# power.net
KiCad netlist of a schematic drawn in Altium Designer
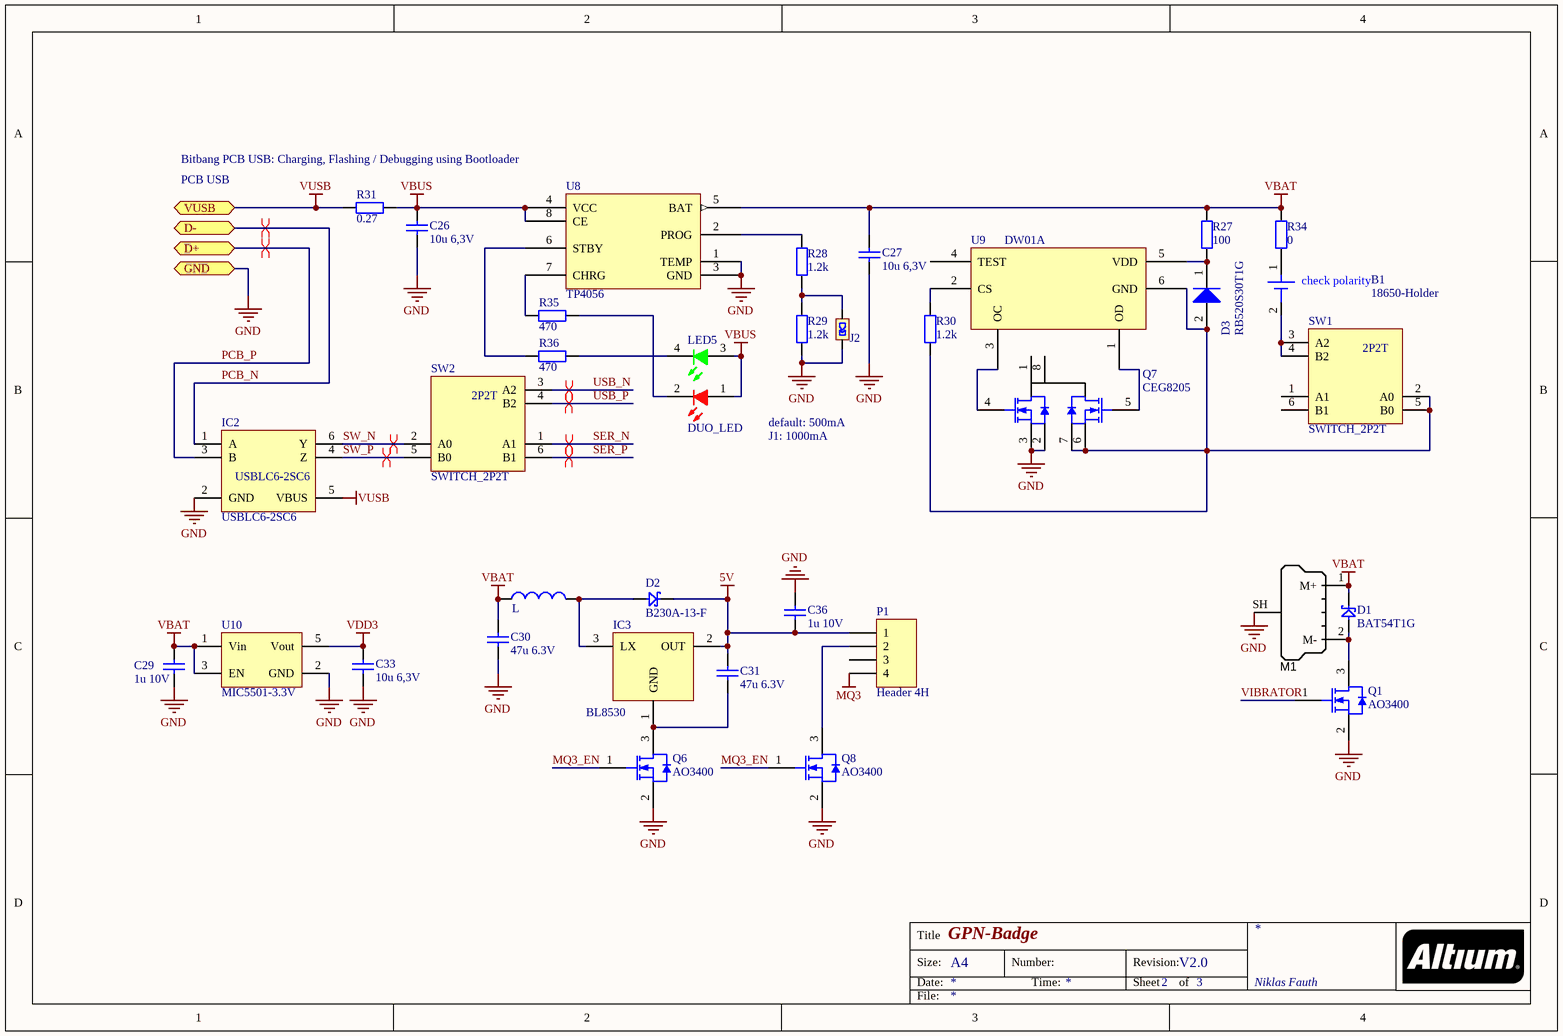
[diagram p0: power.SchDoc]

(export (version "E")
  (design (tool "Eeschema 10.0.6"))
  (components
    (comp (ref "B1")
      (value "18650-Holder")
      (footprint "18650–Holder-SMD")
      (libsource (lib "gpn-badge") (part "18650–Holder"))
    )
    (comp (ref "C26")
      (value "10u 6,3V")
      (footprint "C-0603-H")
      (description "Capacitor 10uF 6,3V")
      (libsource (lib "Passives") (part "C-0603-10u-6,3V"))
    )
    (comp (ref "C27")
      (value "10u 6,3V")
      (footprint "C-0603-H")
      (description "Capacitor 10uF 6,3V")
      (libsource (lib "Passives") (part "C-0603-10u-6,3V"))
    )
    (comp (ref "C29")
      (value "1u 10V")
      (footprint "C-0603-M")
      (description "Capacitor 1uF 10V")
      (libsource (lib "Passives") (part "C-0603-1u-10V"))
    )
    (comp (ref "C30")
      (value "47u 6.3V")
      (footprint "C-0805-M")
      (description "Capacitor 47u 6.3V")
      (libsource (lib "Passives") (part "C-0805-47u-6.3V"))
    )
    (comp (ref "C31")
      (value "47u 6.3V")
      (footprint "C-0805-M")
      (description "Capacitor 47u 6.3V")
      (libsource (lib "Passives") (part "C-0805-47u-6.3V"))
    )
    (comp (ref "C33")
      (value "10u 6,3V")
      (footprint "C-0603-H")
      (description "Capacitor 10uF 6,3V")
      (libsource (lib "Passives") (part "C-0603-10u-6,3V"))
    )
    (comp (ref "C36")
      (value "1u 10V")
      (footprint "C-0603-M")
      (description "Capacitor 1uF 10V")
      (libsource (lib "Passives") (part "C-0603-1u-10V"))
    )
    (comp (ref "D1") (value "BAT54T1G") (footprint "SOD123") (libsource (lib "advanced") (part "D-BAT54T1G")))
    (comp (ref "D2")
      (value "B230A-13-F")
      (footprint "DIODE-SMA")
      (libsource (lib "advanced") (part "D-B230A-13-F"))
    )
    (comp (ref "D3")
      (value "RB520S30T1G")
      (footprint "ONSC-SOD-523-2-502-01_V")
      (description "Schottky Barrier Diode, 2-Pin SOD-523, Pb-Free, Tape and Reel")
      (fields (field (name "MANUFACTURER") "On Semiconductor"))
      (libsource (lib "Altium Content Vault") (part "ONSC-D-K1A2-2"))
    )
    (comp (ref "IC2")
      (value "USBLC6-2SC6")
      (footprint "SOT23-6")
      (description "USB protection")
      (libsource (lib "gpn-badge") (part "USBLC6-2SC6"))
    )
    (comp (ref "IC3")
      (value "BL8530")
      (footprint "SOT89-150P409X160-3N")
      (libsource (lib "gpn-badge") (part "BL8530"))
    )
    (comp (ref "J2")
      (value "jumper")
      (footprint "JUMPER 1-1")
      (libsource (lib "advanced") (part "jumper 1-1"))
    )
    (comp (ref "L1") (value "L") (footprint "L") (libsource (lib "gpn-badge") (part "L")))
    (comp (ref "LED5") (value "DUO_LED") (footprint "LEDDUO") (libsource (lib "gpn-badge") (part "DUO_LED")))
    (comp (ref "M1")
      (value "VIBRATOR")
      (footprint "VIBRATOR_SMD")
      (description "rawr")
      (libsource (lib "gpn-badge") (part "VIBRATOR"))
    )
    (comp (ref "P1")
      (value "Header 4H")
      (footprint "HDR1X4H")
      (description "Header, 4-Pin, Right Angle")
      (fields (field (name "PUBLISHER") "Altium Limited"))
      (libsource (lib "gpn-badge") (part "Header 4H"))
    )
    (comp (ref "Q1")
      (value "AO3400")
      (footprint "AO-SOT23-3_V")
      (description "N-channel Enhancement Mode Field-Effect Transistor; 5.8A/30V")
      (fields (field (name "MANUFACTURER") "Alpha and Omega"))
      (libsource (lib "Altium Content Vault") (part "AO-NEMOS-G1S2D3-3"))
    )
    (comp (ref "Q6")
      (value "AO3400")
      (footprint "AO-SOT23-3_V")
      (description "N-channel Enhancement Mode Field-Effect Transistor; 5.8A/30V")
      (fields (field (name "MANUFACTURER") "Alpha and Omega"))
      (libsource (lib "Altium Content Vault") (part "AO-NEMOS-G1S2D3-3"))
    )
    (comp (ref "Q7")
      (value "CEG8205")
      (footprint "SOP64P640X265-8N")
      (description "Dual mini mosfet 20V 4.5A")
      (libsource (lib "gpn-badge") (part "MOSFET-CEG8205"))
    )
    (comp (ref "Q8")
      (value "AO3400")
      (footprint "AO-SOT23-3_V")
      (description "N-channel Enhancement Mode Field-Effect Transistor; 5.8A/30V")
      (fields (field (name "MANUFACTURER") "Alpha and Omega"))
      (libsource (lib "Altium Content Vault") (part "AO-NEMOS-G1S2D3-3"))
    )
    (comp (ref "R27")
      (value "100")
      (footprint "R-0603-M")
      (description "Resistor 100")
      (libsource (lib "Passives") (part "R-0603-100"))
    )
    (comp (ref "R28")
      (value "1.2k")
      (footprint "R-0603-M")
      (description "Resistor 1.2k")
      (libsource (lib "Passives") (part "R-0603-1k2"))
    )
    (comp (ref "R29")
      (value "1.2k")
      (footprint "R-0603-M")
      (description "Resistor 1.2k")
      (libsource (lib "Passives") (part "R-0603-1k2"))
    )
    (comp (ref "R30")
      (value "1.2k")
      (footprint "R-0603-M")
      (description "Resistor 1.2k")
      (libsource (lib "Passives") (part "R-0603-1k2"))
    )
    (comp (ref "R31")
      (value "0.27")
      (footprint "R-1206-M")
      (description "Resistor 0.27")
      (libsource (lib "Passives") (part "R-1206-0R27"))
    )
    (comp (ref "R34")
      (value "0")
      (footprint "R-0603-M")
      (description "Resistor 0")
      (libsource (lib "Passives") (part "R-0603-0"))
    )
    (comp (ref "R35")
      (value "470")
      (footprint "R-0603-M")
      (description "Resistor 470")
      (libsource (lib "Passives") (part "R-0603-470"))
    )
    (comp (ref "R36")
      (value "470")
      (footprint "R-0603-M")
      (description "Resistor 470")
      (libsource (lib "Passives") (part "R-0603-470"))
    )
    (comp (ref "SW1")
      (value "SWITCH_2P2T")
      (footprint "SWITCH_THT")
      (libsource (lib "gpn-badge") (part "SWITCH_2P2T"))
    )
    (comp (ref "SW2")
      (value "SWITCH_2P2T")
      (footprint "SWITCH_THT")
      (libsource (lib "") (part "SWITCH_2P2T_1"))
    )
    (comp (ref "U8")
      (value "TP4056")
      (footprint "SOIC127P600X20_HS-9N")
      (description "1A standalone linear charging IC")
      (libsource (lib "advanced") (part "TP4056"))
    )
    (comp (ref "U9")
      (value "DW01A")
      (footprint "SOT23-6")
      (description "Single Cell LiIon LiPo Protection")
      (libsource (lib "advanced") (part "DW01A"))
    )
    (comp (ref "U10")
      (value "MIC5501-3.3V")
      (footprint "SOT23-5")
      (libsource (lib "advanced") (part "MIC5501-3.3V"))
    )
  )
  (nets
    (net (code "1") (name "/MQ3_EN") (class "Default")
      (node (ref "Q6") (pin "1") (pinfunction "G_1") (pintype "passive"))
      (node (ref "Q8") (pin "1") (pinfunction "G_1") (pintype "passive"))
    )
    (net (code "2") (name "/PCB_N") (class "Default")
      (node (ref "IC2") (pin "1") (pinfunction "A_1") (pintype "passive"))
    )
    (net (code "3") (name "/PCB_P") (class "Default")
      (node (ref "IC2") (pin "3") (pinfunction "B_3") (pintype "passive"))
    )
    (net (code "4") (name "/SER_N") (class "Default")
      (node (ref "SW2") (pin "1") (pinfunction "A1_1") (pintype "passive"))
    )
    (net (code "5") (name "/SER_P") (class "Default")
      (node (ref "SW2") (pin "6") (pinfunction "B1_6") (pintype "passive"))
    )
    (net (code "6") (name "/SW_N") (class "Default")
      (node (ref "IC2") (pin "6") (pinfunction "Y_6") (pintype "passive"))
      (node (ref "SW2") (pin "2") (pinfunction "A0_2") (pintype "passive"))
    )
    (net (code "7") (name "/SW_P") (class "Default")
      (node (ref "IC2") (pin "4") (pinfunction "Z_4") (pintype "passive"))
      (node (ref "SW2") (pin "5") (pinfunction "B0_5") (pintype "passive"))
    )
    (net (code "8") (name "/USB_N") (class "Default")
      (node (ref "SW2") (pin "3") (pinfunction "A2_3") (pintype "passive"))
    )
    (net (code "9") (name "/USB_P") (class "Default")
      (node (ref "SW2") (pin "4") (pinfunction "B2_4") (pintype "passive"))
    )
    (net (code "10") (name "/VIBRATOR") (class "Default")
      (node (ref "Q1") (pin "1") (pinfunction "G_1") (pintype "passive"))
    )
    (net (code "11") (name "5V") (class "Default")
      (node (ref "C31") (pin "2") (pinfunction "2_2") (pintype "passive"))
      (node (ref "C36") (pin "2") (pinfunction "2_2") (pintype "passive"))
      (node (ref "D2") (pin "2") (pinfunction "kt_2") (pintype "passive"))
      (node (ref "IC3") (pin "2") (pinfunction "OUT_2") (pintype "passive"))
      (node (ref "P1") (pin "1") (pinfunction "1_1") (pintype "passive"))
    )
    (net (code "12") (name "GND") (class "Default")
      (node (ref "C26") (pin "1") (pinfunction "1_1") (pintype "passive"))
      (node (ref "C27") (pin "1") (pinfunction "1_1") (pintype "passive"))
      (node (ref "C29") (pin "1") (pinfunction "1_1") (pintype "passive"))
      (node (ref "C30") (pin "1") (pinfunction "1_1") (pintype "passive"))
      (node (ref "C33") (pin "1") (pinfunction "1_1") (pintype "passive"))
      (node (ref "C36") (pin "1") (pinfunction "1_1") (pintype "passive"))
      (node (ref "IC2") (pin "2") (pinfunction "GND_2") (pintype "passive"))
      (node (ref "J2") (pin "2") (pintype "passive"))
      (node (ref "M1") (pin "SH") (pinfunction "Shell_SH") (pintype "passive"))
      (node (ref "Q1") (pin "2") (pinfunction "S_2") (pintype "passive"))
      (node (ref "Q6") (pin "2") (pinfunction "S_2") (pintype "passive"))
      (node (ref "Q7") (pin "2") (pinfunction "S1_2") (pintype "passive"))
      (node (ref "Q7") (pin "3") (pinfunction "S1_3") (pintype "passive"))
      (node (ref "Q8") (pin "2") (pinfunction "S_2") (pintype "passive"))
      (node (ref "R29") (pin "1") (pinfunction "1_1") (pintype "passive"))
      (node (ref "U10") (pin "2") (pinfunction "GND_2") (pintype "passive"))
      (node (ref "U8") (pin "1") (pinfunction "TEMP_1") (pintype "passive"))
      (node (ref "U8") (pin "3") (pinfunction "GND_3") (pintype "power_in"))
    )
    (net (code "13") (name "MQ3") (class "Default")
      (node (ref "P1") (pin "4") (pinfunction "4_4") (pintype "passive"))
    )
    (net (code "14") (name "Net-(B1-Pad1)") (class "Default")
      (node (ref "B1") (pin "1") (pintype "passive"))
      (node (ref "R34") (pin "1") (pinfunction "1_1") (pintype "passive"))
    )
    (net (code "15") (name "Net-(D1-an)") (class "Default")
      (node (ref "D1") (pin "1") (pinfunction "an_1") (pintype "passive"))
      (node (ref "M1") (pin "2") (pinfunction "M-_2") (pintype "passive"))
      (node (ref "Q1") (pin "3") (pinfunction "D_3") (pintype "passive"))
    )
    (net (code "16") (name "Net-(D2-an)") (class "Default")
      (node (ref "D2") (pin "1") (pinfunction "an_1") (pintype "passive"))
      (node (ref "IC3") (pin "3") (pinfunction "LX_3") (pintype "passive"))
      (node (ref "L1") (pin "2") (pinfunction "2_2") (pintype "passive"))
    )
    (net (code "17") (name "Net-(D3-A)") (class "Default")
      (node (ref "D3") (pin "2") (pinfunction "A_2") (pintype "passive"))
      (node (ref "Q7") (pin "6") (pinfunction "S2_6") (pintype "passive"))
      (node (ref "Q7") (pin "7") (pinfunction "S2_7") (pintype "passive"))
      (node (ref "R30") (pin "1") (pinfunction "1_1") (pintype "passive"))
      (node (ref "SW1") (pin "2") (pinfunction "A0_2") (pintype "passive"))
      (node (ref "SW1") (pin "5") (pinfunction "B0_5") (pintype "passive"))
      (node (ref "U9") (pin "6") (pinfunction "GND_6") (pintype "passive"))
    )
    (net (code "18") (name "Net-(D3-K)") (class "Default")
      (node (ref "D3") (pin "1") (pinfunction "K_1") (pintype "passive"))
      (node (ref "R27") (pin "1") (pinfunction "1_1") (pintype "passive"))
      (node (ref "U9") (pin "5") (pinfunction "VDD_5") (pintype "passive"))
    )
    (net (code "19") (name "Net-(IC3-GND)") (class "Default")
      (node (ref "C31") (pin "1") (pinfunction "1_1") (pintype "passive"))
      (node (ref "IC3") (pin "1") (pinfunction "GND_1") (pintype "passive"))
      (node (ref "Q6") (pin "3") (pinfunction "D_3") (pintype "passive"))
    )
    (net (code "20") (name "Net-(J2-Pad1)") (class "Default")
      (node (ref "J2") (pin "1") (pintype "passive"))
      (node (ref "R28") (pin "1") (pinfunction "1_1") (pintype "passive"))
      (node (ref "R29") (pin "2") (pinfunction "2_2") (pintype "passive"))
    )
    (net (code "21") (name "Net-(LED5-K-Pad2)") (class "Default")
      (node (ref "LED5") (pin "2") (pinfunction "K_2") (pintype "passive"))
      (node (ref "R35") (pin "2") (pinfunction "2_2") (pintype "passive"))
    )
    (net (code "22") (name "Net-(LED5-K-Pad4)") (class "Default")
      (node (ref "LED5") (pin "4") (pinfunction "K_4") (pintype "passive"))
      (node (ref "R36") (pin "2") (pinfunction "2_2") (pintype "passive"))
    )
    (net (code "23") (name "Net-(Q7-G1)") (class "Default")
      (node (ref "Q7") (pin "4") (pinfunction "G1_4") (pintype "passive"))
      (node (ref "U9") (pin "3") (pinfunction "OC_3") (pintype "passive"))
    )
    (net (code "24") (name "Net-(Q7-G2)") (class "Default")
      (node (ref "Q7") (pin "5") (pinfunction "G2_5") (pintype "passive"))
      (node (ref "U9") (pin "1") (pinfunction "OD_1") (pintype "passive"))
    )
    (net (code "25") (name "Net-(Q8-D)") (class "Default")
      (node (ref "P1") (pin "2") (pinfunction "2_2") (pintype "passive"))
      (node (ref "Q8") (pin "3") (pinfunction "D_3") (pintype "passive"))
    )
    (net (code "26") (name "Net-(SW1-A2)") (class "Default")
      (node (ref "B1") (pin "2") (pintype "passive"))
      (node (ref "SW1") (pin "3") (pinfunction "A2_3") (pintype "passive"))
      (node (ref "SW1") (pin "4") (pinfunction "B2_4") (pintype "passive"))
    )
    (net (code "27") (name "Net-(U8-CHRG)") (class "Default")
      (node (ref "R35") (pin "1") (pinfunction "1_1") (pintype "passive"))
      (node (ref "U8") (pin "7") (pinfunction "CHRG_7") (pintype "passive"))
    )
    (net (code "28") (name "Net-(U8-PROG)") (class "Default")
      (node (ref "R28") (pin "2") (pinfunction "2_2") (pintype "passive"))
      (node (ref "U8") (pin "2") (pinfunction "PROG_2") (pintype "passive"))
    )
    (net (code "29") (name "Net-(U8-STBY)") (class "Default")
      (node (ref "R36") (pin "1") (pinfunction "1_1") (pintype "passive"))
      (node (ref "U8") (pin "6") (pinfunction "STBY_6") (pintype "passive"))
    )
    (net (code "30") (name "Net-(U9-CS)") (class "Default")
      (node (ref "R30") (pin "2") (pinfunction "2_2") (pintype "passive"))
      (node (ref "U9") (pin "2") (pinfunction "CS_2") (pintype "passive"))
    )
    (net (code "31") (name "VBAT") (class "Default")
      (node (ref "C27") (pin "2") (pinfunction "2_2") (pintype "passive"))
      (node (ref "C29") (pin "2") (pinfunction "2_2") (pintype "passive"))
      (node (ref "C30") (pin "2") (pinfunction "2_2") (pintype "passive"))
      (node (ref "D1") (pin "2") (pinfunction "kt_2") (pintype "passive"))
      (node (ref "L1") (pin "1") (pinfunction "1_1") (pintype "passive"))
      (node (ref "M1") (pin "1") (pinfunction "M+_1") (pintype "passive"))
      (node (ref "R27") (pin "2") (pinfunction "2_2") (pintype "passive"))
      (node (ref "R34") (pin "2") (pinfunction "2_2") (pintype "passive"))
      (node (ref "U10") (pin "1") (pinfunction "Vin_1") (pintype "passive"))
      (node (ref "U10") (pin "3") (pinfunction "EN_3") (pintype "passive"))
      (node (ref "U8") (pin "5") (pinfunction "BAT_5") (pintype "output"))
    )
    (net (code "32") (name "VBUS") (class "Default")
      (node (ref "C26") (pin "2") (pinfunction "2_2") (pintype "passive"))
      (node (ref "LED5") (pin "1") (pinfunction "A_1") (pintype "passive"))
      (node (ref "LED5") (pin "3") (pinfunction "A_3") (pintype "passive"))
      (node (ref "R31") (pin "2") (pinfunction "2_2") (pintype "passive"))
      (node (ref "U8") (pin "4") (pinfunction "VCC_4") (pintype "passive"))
      (node (ref "U8") (pin "8") (pinfunction "CE_8") (pintype "passive"))
    )
    (net (code "33") (name "VDD3") (class "Default")
      (node (ref "C33") (pin "2") (pinfunction "2_2") (pintype "passive"))
      (node (ref "U10") (pin "5") (pinfunction "Vout_5") (pintype "passive"))
    )
    (net (code "34") (name "VUSB") (class "Default")
      (node (ref "IC2") (pin "5") (pinfunction "VBUS_5") (pintype "passive"))
      (node (ref "R31") (pin "1") (pinfunction "1_1") (pintype "passive"))
    )
    (net (code "35") (name "unconnected-(P1-Pad3)") (class "Default")
      (node (ref "P1") (pin "3") (pinfunction "3_3") (pintype "passive"))
    )
    (net (code "36") (name "unconnected-(Q7-D-Pad8)") (class "Default")
      (node (ref "Q7") (pin "8") (pinfunction "D_8") (pintype "passive"))
    )
    (net (code "37") (name "unconnected-(Q7-S-Pad1)") (class "Default")
      (node (ref "Q7") (pin "1") (pinfunction "S_1") (pintype "passive"))
    )
    (net (code "38") (name "unconnected-(SW1-A1-Pad1)") (class "Default")
      (node (ref "SW1") (pin "1") (pinfunction "A1_1") (pintype "passive"))
    )
    (net (code "39") (name "unconnected-(SW1-B1-Pad6)") (class "Default")
      (node (ref "SW1") (pin "6") (pinfunction "B1_6") (pintype "passive"))
    )
    (net (code "40") (name "unconnected-(U9-TEST-Pad4)") (class "Default")
      (node (ref "U9") (pin "4") (pinfunction "TEST_4") (pintype "passive"))
    )
  )
)
